# SD-TF.net
KiCad netlist of a schematic drawn in Altium Designer
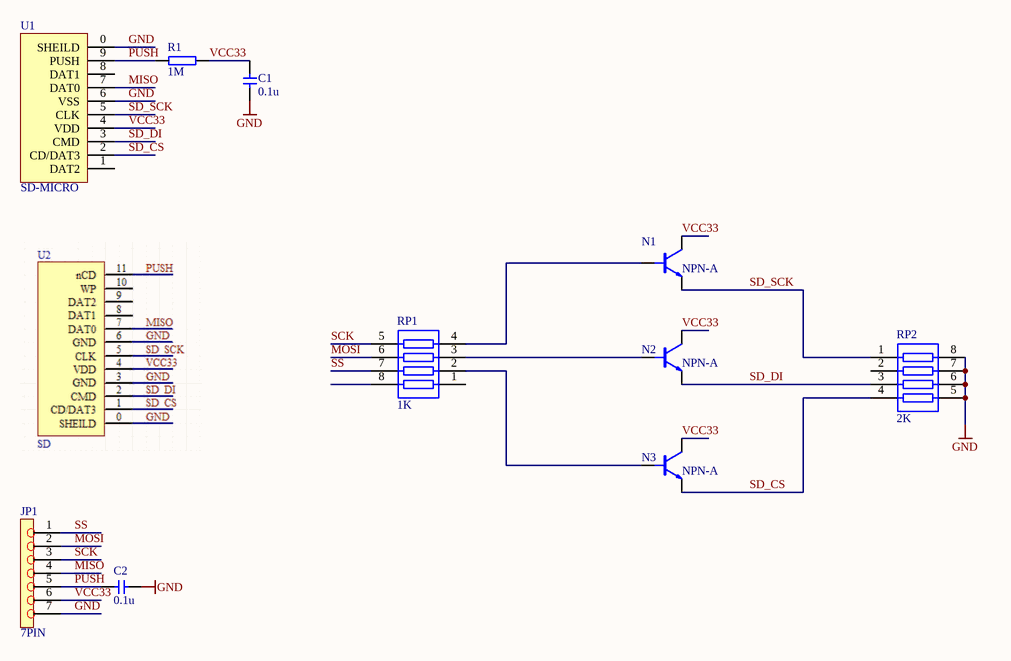
[diagram p0: SD-TF.SchDoc]

(export (version "E")
  (design (tool "Eeschema 10.0.6"))
  (components
    (comp (ref "C1") (value "0.1u") (footprint "RC100") (libsource (lib "Common") (part "CAPA")))
    (comp (ref "C2") (value "0.1u") (footprint "0805") (libsource (lib "Common") (part "CAPA")))
    (comp (ref "JP1") (value "7PIN") (footprint "SIP7") (libsource (lib "Common") (part "7PIN")))
    (comp (ref "N1") (value "NPN-A") (footprint "SOT-23A") (libsource (lib "三极管&二极管") (part "NPN-A")))
    (comp (ref "N2") (value "NPN-A") (footprint "SOT-23A") (libsource (lib "三极管&二极管") (part "NPN-A")))
    (comp (ref "N3") (value "NPN-A") (footprint "SOT-23A") (libsource (lib "三极管&二极管") (part "NPN-A")))
    (comp (ref "R1") (value "1M") (footprint "0805") (libsource (lib "Common") (part "RES2A")))
    (comp (ref "RP1") (value "1K") (footprint "RN4") (libsource (lib "Common") (part "RESPACK4")))
    (comp (ref "RP2") (value "2K") (footprint "RN4") (libsource (lib "Common") (part "RESPACK4")))
    (comp (ref "U1") (value "SD-MICRO") (footprint "TF-2") (libsource (lib "Common") (part "SD-MICRO")))
  )
  (nets
    (net (code "1") (name "/MISO") (class "Default")
      (node (ref "JP1") (pin "4") (pintype "passive"))
      (node (ref "U1") (pin "7") (pinfunction "DAT0_7") (pintype "passive"))
    )
    (net (code "2") (name "/MOSI") (class "Default")
      (node (ref "JP1") (pin "2") (pintype "passive"))
      (node (ref "RP1") (pin "6") (pintype "passive"))
    )
    (net (code "3") (name "/PUSH") (class "Default")
      (node (ref "C2") (pin "1") (pintype "passive"))
      (node (ref "JP1") (pin "5") (pintype "passive"))
      (node (ref "R1") (pin "2") (pintype "passive"))
      (node (ref "U1") (pin "9") (pinfunction "PUSH_9") (pintype "passive"))
    )
    (net (code "4") (name "/SCK") (class "Default")
      (node (ref "JP1") (pin "3") (pintype "passive"))
      (node (ref "RP1") (pin "5") (pintype "passive"))
    )
    (net (code "5") (name "/SD_CS") (class "Default")
      (node (ref "N3") (pin "E") (pintype "passive"))
      (node (ref "RP2") (pin "4") (pintype "passive"))
      (node (ref "U1") (pin "2") (pinfunction "CD/DAT3_2") (pintype "passive"))
    )
    (net (code "6") (name "/SD_DI") (class "Default")
      (node (ref "N2") (pin "E") (pintype "passive"))
      (node (ref "RP2") (pin "3") (pintype "passive"))
      (node (ref "U1") (pin "3") (pinfunction "CMD_3") (pintype "passive"))
    )
    (net (code "7") (name "/SD_SCK") (class "Default")
      (node (ref "N1") (pin "E") (pintype "passive"))
      (node (ref "RP2") (pin "1") (pintype "passive"))
      (node (ref "U1") (pin "5") (pinfunction "CLK_5") (pintype "passive"))
    )
    (net (code "8") (name "/SS") (class "Default")
      (node (ref "JP1") (pin "1") (pintype "passive"))
      (node (ref "RP1") (pin "7") (pintype "passive"))
    )
    (net (code "9") (name "/VCC33") (class "Default")
      (node (ref "C1") (pin "1") (pintype "passive"))
      (node (ref "JP1") (pin "6") (pintype "passive"))
      (node (ref "N1") (pin "C") (pintype "passive"))
      (node (ref "N2") (pin "C") (pintype "passive"))
      (node (ref "N3") (pin "C") (pintype "passive"))
      (node (ref "R1") (pin "1") (pintype "passive"))
      (node (ref "U1") (pin "4") (pinfunction "VDD_4") (pintype "passive"))
    )
    (net (code "10") (name "GND") (class "Default")
      (node (ref "C1") (pin "2") (pintype "passive"))
      (node (ref "C2") (pin "2") (pintype "passive"))
      (node (ref "JP1") (pin "7") (pintype "passive"))
      (node (ref "RP2") (pin "5") (pintype "passive"))
      (node (ref "RP2") (pin "6") (pintype "passive"))
      (node (ref "RP2") (pin "7") (pintype "passive"))
      (node (ref "RP2") (pin "8") (pintype "passive"))
      (node (ref "U1") (pin "0") (pinfunction "SHEILD_0") (pintype "passive"))
      (node (ref "U1") (pin "6") (pinfunction "VSS_6") (pintype "passive"))
    )
    (net (code "11") (name "Net-(N1-PadB)") (class "Default")
      (node (ref "N1") (pin "B") (pintype "passive"))
      (node (ref "RP1") (pin "4") (pintype "passive"))
    )
    (net (code "12") (name "Net-(N2-PadB)") (class "Default")
      (node (ref "N2") (pin "B") (pintype "passive"))
      (node (ref "RP1") (pin "3") (pintype "passive"))
    )
    (net (code "13") (name "Net-(N3-PadB)") (class "Default")
      (node (ref "N3") (pin "B") (pintype "passive"))
      (node (ref "RP1") (pin "2") (pintype "passive"))
    )
    (net (code "14") (name "unconnected-(RP1-Pad1)") (class "Default")
      (node (ref "RP1") (pin "1") (pintype "passive"))
    )
    (net (code "15") (name "unconnected-(RP1-Pad8)") (class "Default")
      (node (ref "RP1") (pin "8") (pintype "passive"))
    )
    (net (code "16") (name "unconnected-(RP2-Pad2)") (class "Default")
      (node (ref "RP2") (pin "2") (pintype "passive"))
    )
    (net (code "17") (name "unconnected-(U1-DAT1-Pad8)") (class "Default")
      (node (ref "U1") (pin "8") (pinfunction "DAT1_8") (pintype "passive"))
    )
    (net (code "18") (name "unconnected-(U1-DAT2-Pad1)") (class "Default")
      (node (ref "U1") (pin "1") (pinfunction "DAT2_1") (pintype "passive"))
    )
  )
)
